# simple-buffer-with-jacks-V0-2.net
KiCad netlist of a schematic drawn in EAGLE
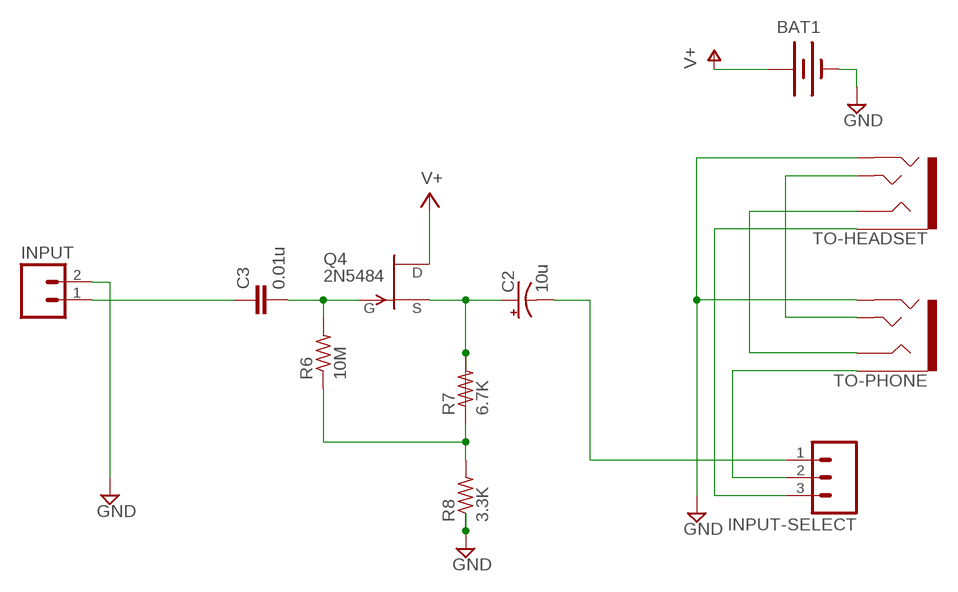
[diagram p0: schematic, sheet 1]

(export (version "E")
  (design (tool "Eeschema 10.0.6"))
  (components
    (comp (ref "BAT1")
      (value "BATTERYAAA-KIT")
      (footprint "eagle-import:BATTERY-AAA-KIT")
      (libsource (lib "eagle-import") (part "BATTERYAAA-KIT"))
    )
    (comp (ref "C2")
      (value "10u")
      (footprint "eagle-import:CPOL-RADIAL-10UF-25V")
      (libsource (lib "eagle-import") (part "CAP_POLPTH2"))
    )
    (comp (ref "C3")
      (value "0.01u")
      (footprint "eagle-import:C5B3")
      (libsource (lib "eagle-import") (part "C5/3"))
    )
    (comp (ref "INPUT")
      (value "M02LOCK")
      (footprint "eagle-import:1X02_LOCK")
      (libsource (lib "eagle-import") (part "M02LOCK"))
    )
    (comp (ref "INPUT-SELECT")
      (value "M03LOCK")
      (footprint "eagle-import:1X03_LOCK")
      (libsource (lib "eagle-import") (part "M03LOCK"))
    )
    (comp (ref "Q4")
      (value "2N5484")
      (footprint "eagle-import:TO92-")
      (libsource (lib "eagle-import") (part "?5482N4"))
    )
    (comp (ref "R6")
      (value "10M")
      (footprint "eagle-import:0414V")
      (libsource (lib "eagle-import") (part "R-US_0414/5V"))
    )
    (comp (ref "R7")
      (value "6.7K")
      (footprint "eagle-import:0414V")
      (libsource (lib "eagle-import") (part "R-US_0414/5V"))
    )
    (comp (ref "R8")
      (value "3.3K")
      (footprint "eagle-import:0414V")
      (libsource (lib "eagle-import") (part "R-US_0414/5V"))
    )
    (comp (ref "TO-HEADSET")
      (value "AUDIO-JACK3")
      (footprint "eagle-import:AUDIO-JACK-TRRS-SMD")
      (libsource (lib "eagle-import") (part "AUDIO-JACK3"))
    )
    (comp (ref "TO-PHONE")
      (value "AUDIO-JACK3")
      (footprint "eagle-import:AUDIO-JACK-TRRS-SMD")
      (libsource (lib "eagle-import") (part "AUDIO-JACK3"))
    )
  )
  (nets
    (net (code "1") (name "GND") (class "Default")
      (node (ref "BAT1") (pin "GND@1") (pinfunction "-_GND@1") (pintype "power_in"))
      (node (ref "INPUT") (pin "2") (pinfunction "2_2") (pintype "passive"))
      (node (ref "R8") (pin "1") (pinfunction "1_1") (pintype "passive"))
      (node (ref "TO-HEADSET") (pin "RING2") (pinfunction "RING2_RING2") (pintype "bidirectional"))
      (node (ref "TO-PHONE") (pin "RING2") (pinfunction "RING2_RING2") (pintype "bidirectional"))
    )
    (net (code "2") (name "Net-(C2-+)") (class "Default")
      (node (ref "C2") (pin "1") (pinfunction "+_1") (pintype "passive"))
      (node (ref "Q4") (pin "2") (pinfunction "S_2") (pintype "passive"))
      (node (ref "R7") (pin "2") (pinfunction "2_2") (pintype "passive"))
    )
    (net (code "3") (name "Net-(C2--)") (class "Default")
      (node (ref "C2") (pin "2") (pinfunction "-_2") (pintype "passive"))
      (node (ref "INPUT-SELECT") (pin "1") (pinfunction "1_1") (pintype "passive"))
    )
    (net (code "4") (name "Net-(C3-Pad1)") (class "Default")
      (node (ref "C3") (pin "1") (pinfunction "1_1") (pintype "passive"))
      (node (ref "INPUT") (pin "1") (pinfunction "1_1") (pintype "passive"))
    )
    (net (code "5") (name "Net-(INPUT-SELECT-Pad2)") (class "Default")
      (node (ref "INPUT-SELECT") (pin "2") (pinfunction "2_2") (pintype "passive"))
      (node (ref "TO-PHONE") (pin "EARTH") (pinfunction "EARTH_EARTH") (pintype "bidirectional"))
    )
    (net (code "6") (name "Net-(INPUT-SELECT-Pad3)") (class "Default")
      (node (ref "INPUT-SELECT") (pin "3") (pinfunction "3_3") (pintype "passive"))
      (node (ref "TO-HEADSET") (pin "EARTH") (pinfunction "EARTH_EARTH") (pintype "bidirectional"))
    )
    (net (code "7") (name "Net-(Q4-G)") (class "Default")
      (node (ref "C3") (pin "2") (pinfunction "2_2") (pintype "passive"))
      (node (ref "Q4") (pin "1") (pinfunction "G_1") (pintype "passive"))
      (node (ref "R6") (pin "2") (pinfunction "2_2") (pintype "passive"))
    )
    (net (code "8") (name "Net-(R6-Pad1)") (class "Default")
      (node (ref "R6") (pin "1") (pinfunction "1_1") (pintype "passive"))
      (node (ref "R7") (pin "1") (pinfunction "1_1") (pintype "passive"))
      (node (ref "R8") (pin "2") (pinfunction "2_2") (pintype "passive"))
    )
    (net (code "9") (name "Net-(TO-HEADSET-PadRING1)") (class "Default")
      (node (ref "TO-HEADSET") (pin "RING1") (pinfunction "RING1_RING1") (pintype "bidirectional"))
      (node (ref "TO-PHONE") (pin "RING1") (pinfunction "RING1_RING1") (pintype "bidirectional"))
    )
    (net (code "10") (name "Net-(TO-HEADSET-PadTIP)") (class "Default")
      (node (ref "TO-HEADSET") (pin "TIP") (pinfunction "TIP_TIP") (pintype "bidirectional"))
      (node (ref "TO-PHONE") (pin "TIP") (pinfunction "TIP_TIP") (pintype "bidirectional"))
    )
    (net (code "11") (name "V+") (class "Default")
      (node (ref "BAT1") (pin "PWR@1") (pinfunction "+_PWR@1") (pintype "power_in"))
      (node (ref "Q4") (pin "3") (pinfunction "D_3") (pintype "passive"))
    )
  )
)
